# Mainboard_ThermistorAmp.net
KiCad netlist of a schematic drawn in Altium Designer
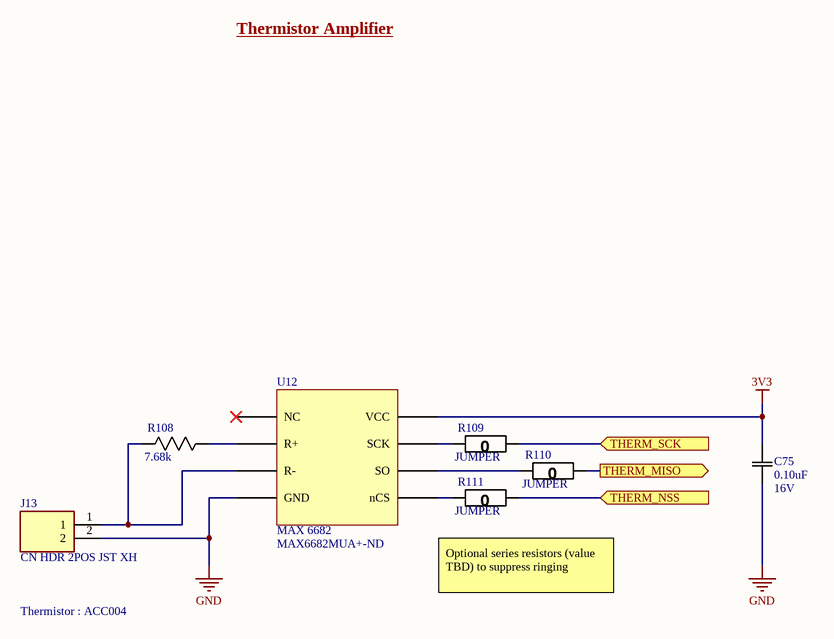
[diagram p0: Mainboard_ThermistorAmp.SchDoc]

(export (version "E")
  (design (tool "Eeschema 10.0.6"))
  (components
    (comp (ref "C75")
      (value "0.10uF")
      (footprint "0603")
      (description "CAP CER 0.10UF 16V X5R 0603/0805")
      (fields (field (name "TOLERANCE") "10%") (field (name "RATING") "16V"))
      (libsource (lib "AltiumLibraries") (part "CAP 0.10uF 16V"))
    )
    (comp (ref "J13")
      (value "CN HDR 2POS JST XH")
      (footprint "JST_B2B-XH-A(LF)(SN)")
      (description "Connector Header Through Hole 2 position 0.098 _2.50mm_\r\nJST XH")
      (fields (field (name "MP") "B2B-XH-A_LF__SN_") (field (name "MF") "JST Sales"))
      (libsource (lib "AltiumLibraries") (part "CN HDR 2POS JST XH"))
    )
    (comp (ref "R108")
      (value "7.68k")
      (footprint "0805")
      (description "RES SMD 7.68K OHM 0.1% 0.15W 0805")
      (fields (field (name "TOLERANCE") "5%"))
      (libsource (lib "AltiumLibraries") (part "RES 7.68k 0.15W"))
    )
    (comp (ref "R109")
      (value "JUMPER")
      (footprint "0603")
      (description "RES SMD 0 OHM JUMPER GENERIC 0805")
      (libsource (lib "AltiumLibraries") (part "RES 0 JUMPER"))
    )
    (comp (ref "R110")
      (value "JUMPER")
      (footprint "0603")
      (description "RES SMD 0 OHM JUMPER GENERIC 0805")
      (libsource (lib "AltiumLibraries") (part "RES 0 JUMPER"))
    )
    (comp (ref "R111")
      (value "JUMPER")
      (footprint "0603")
      (description "RES SMD 0 OHM JUMPER GENERIC 0805")
      (libsource (lib "AltiumLibraries") (part "RES 0 JUMPER"))
    )
    (comp (ref "U12")
      (value "MAX 6682")
      (footprint "8-MSOP")
      (description "MAX 6685 Thermistor - SPI converter, 8bit")
      (fields (field (name "SUPPLIER PART NUMBER 1") "MAX6682MUA+-ND"))
      (libsource (lib "AltiumLibraries") (part "MAX 6682"))
    )
  )
  (nets
    (net (code "1") (name "/THERM_MISO") (class "Default")
      (node (ref "R110") (pin "1") (pinfunction "R1_1") (pintype "passive"))
    )
    (net (code "2") (name "/THERM_NSS") (class "Default")
      (node (ref "R111") (pin "1") (pinfunction "R1_1") (pintype "passive"))
    )
    (net (code "3") (name "/THERM_SCK") (class "Default")
      (node (ref "R109") (pin "1") (pinfunction "R1_1") (pintype "passive"))
    )
    (net (code "4") (name "3V3") (class "Default")
      (node (ref "C75") (pin "1") (pinfunction "C1_1") (pintype "passive"))
      (node (ref "U12") (pin "8") (pinfunction "VCC_8") (pintype "passive"))
    )
    (net (code "5") (name "GND") (class "Default")
      (node (ref "C75") (pin "2") (pinfunction "C2_2") (pintype "passive"))
      (node (ref "J13") (pin "2") (pinfunction "2_2") (pintype "passive"))
      (node (ref "U12") (pin "4") (pinfunction "GND_4") (pintype "passive"))
    )
    (net (code "6") (name "Net-(R108-R1)") (class "Default")
      (node (ref "R108") (pin "1") (pinfunction "R1_1") (pintype "passive"))
      (node (ref "U12") (pin "2") (pinfunction "R+_2") (pintype "passive"))
    )
    (net (code "7") (name "Net-(R108-R2)") (class "Default")
      (node (ref "J13") (pin "1") (pinfunction "1_1") (pintype "passive"))
      (node (ref "R108") (pin "2") (pinfunction "R2_2") (pintype "passive"))
      (node (ref "U12") (pin "3") (pinfunction "R-_3") (pintype "passive"))
    )
    (net (code "8") (name "Net-(R109-R2)") (class "Default")
      (node (ref "R109") (pin "2") (pinfunction "R2_2") (pintype "passive"))
      (node (ref "U12") (pin "7") (pinfunction "SCK_7") (pintype "passive"))
    )
    (net (code "9") (name "Net-(R110-R2)") (class "Default")
      (node (ref "R110") (pin "2") (pinfunction "R2_2") (pintype "passive"))
      (node (ref "U12") (pin "6") (pinfunction "SO_6") (pintype "passive"))
    )
    (net (code "10") (name "Net-(R111-R2)") (class "Default")
      (node (ref "R111") (pin "2") (pinfunction "R2_2") (pintype "passive"))
      (node (ref "U12") (pin "5") (pinfunction "nCS_5") (pintype "passive"))
    )
    (net (code "11") (name "unconnected-(U12-NC-Pad1)") (class "Default")
      (node (ref "U12") (pin "1") (pinfunction "NC_1") (pintype "passive+no_connect"))
    )
  )
)
